# ftdi.net
KiCad netlist of a schematic drawn in Altium Designer
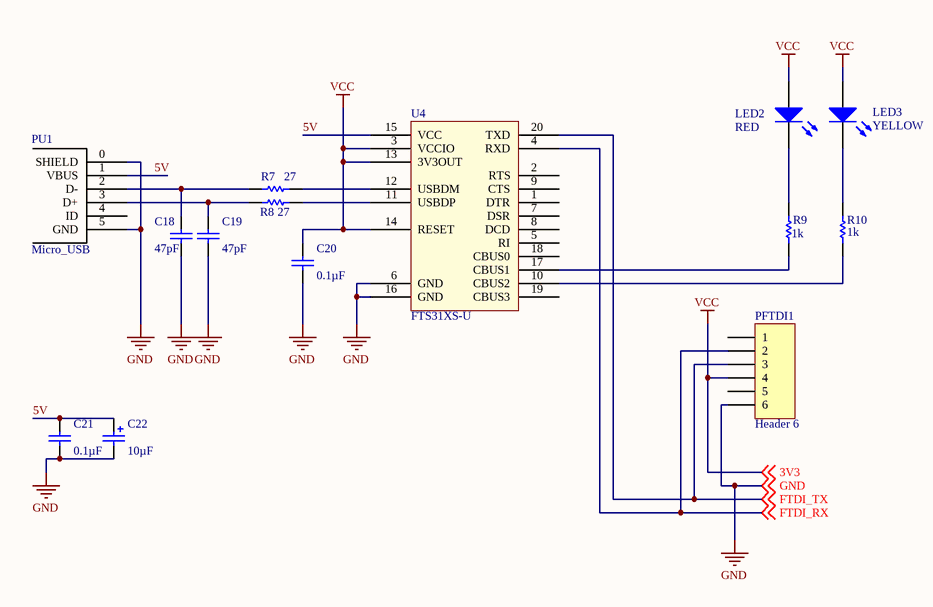
[diagram p0: ftdi.SchDoc]

(export (version "E")
  (design (tool "Eeschema 10.0.6"))
  (components
    (comp (ref "C18")
      (value "47pF")
      (footprint "0805-C")
      (description "Capacitor")
      (fields (field (name "Comment") "Cap") (field (name "PUBLISHER") "Altium Limited"))
      (libsource (lib "Miscellaneous Devices") (part "Cap"))
    )
    (comp (ref "C19")
      (value "47pF")
      (footprint "0805-C")
      (description "Capacitor")
      (fields (field (name "Comment") "Cap") (field (name "PUBLISHER") "Altium Limited"))
      (libsource (lib "Miscellaneous Devices") (part "Cap"))
    )
    (comp (ref "C20")
      (value "0.1µF")
      (footprint "0805-C")
      (description "Capacitor")
      (fields (field (name "Comment") "Cap") (field (name "PUBLISHER") "Altium Limited"))
      (libsource (lib "Miscellaneous Devices") (part "Cap"))
    )
    (comp (ref "C21")
      (value "0.1µF")
      (footprint "0805-C")
      (description "Capacitor")
      (fields (field (name "Comment") "Cap") (field (name "PUBLISHER") "Altium Limited"))
      (libsource (lib "Miscellaneous Devices") (part "Cap"))
    )
    (comp (ref "C22")
      (value "10µF")
      (footprint "0805-TC")
      (description "Polarized Capacitor (Radial)")
      (fields (field (name "Comment") "Cap Pol1") (field (name "PUBLISHER") "Altium Limited"))
      (libsource (lib "Miscellaneous Devices") (part "Cap Pol1"))
    )
    (comp (ref "LED2")
      (value "RED")
      (footprint "0805-LED")
      (description "Typical RED, GREEN, YELLOW, AMBER GaAs LED")
      (fields (field (name "PUBLISHER") "Altium Limited"))
      (libsource (lib "Miscellaneous Devices") (part "LED2"))
    )
    (comp (ref "LED3")
      (value "YELLOW")
      (footprint "0805-LED")
      (description "Typical RED, GREEN, YELLOW, AMBER GaAs LED")
      (fields (field (name "PUBLISHER") "Altium Limited"))
      (libsource (lib "Miscellaneous Devices") (part "LED2"))
    )
    (comp (ref "PFTDI1")
      (value "Header 6")
      (footprint "HDR1X6")
      (description "Header, 6-Pin")
      (fields (field (name "PUBLISHER") "Altium Limited"))
      (libsource (lib "Miscellaneous Connectors") (part "Header 6"))
    )
    (comp (ref "PU1")
      (value "Micro_USB")
      (footprint "Micro_USB")
      (libsource (lib "Micro_USB") (part "Micro_USB"))
    )
    (comp (ref "R7")
      (value "27")
      (footprint "0805-R")
      (description "Resistor")
      (fields (field (name "Comment") "Res1") (field (name "PUBLISHER") "Altium Limited"))
      (libsource (lib "Miscellaneous Devices") (part "Res1"))
    )
    (comp (ref "R8")
      (value "27")
      (footprint "0805-R")
      (description "Resistor")
      (fields (field (name "Comment") "Res1") (field (name "PUBLISHER") "Altium Limited"))
      (libsource (lib "Miscellaneous Devices") (part "Res1"))
    )
    (comp (ref "R9")
      (value "1k")
      (footprint "0805-R")
      (description "Resistor")
      (fields (field (name "Comment") "Res1") (field (name "PUBLISHER") "Altium Limited"))
      (libsource (lib "Miscellaneous Devices") (part "Res1"))
    )
    (comp (ref "R10")
      (value "1k")
      (footprint "0805-R")
      (description "Resistor")
      (fields (field (name "Comment") "Res1") (field (name "PUBLISHER") "Altium Limited"))
      (libsource (lib "Miscellaneous Devices") (part "Res1"))
    )
    (comp (ref "U4")
      (value "FTS31XS-U")
      (footprint "SOP64P570X175-20N")
      (libsource (lib "FTS31XS-U") (part "FTS31XS-U"))
    )
  )
  (nets
    (net (code "1") (name "/5V") (class "Default")
      (node (ref "C21") (pin "2") (pinfunction "2_2") (pintype "passive"))
      (node (ref "C22") (pin "1") (pinfunction "1_1") (pintype "passive"))
      (node (ref "PU1") (pin "1") (pinfunction "VBUS_1") (pintype "passive"))
      (node (ref "U4") (pin "15") (pinfunction "VCC_15") (pintype "passive"))
    )
    (net (code "2") (name "3V3") (class "Default")
      (node (ref "C20") (pin "2") (pinfunction "2_2") (pintype "passive"))
      (node (ref "LED2") (pin "1") (pinfunction "A_1") (pintype "passive"))
      (node (ref "LED3") (pin "1") (pinfunction "A_1") (pintype "passive"))
      (node (ref "PFTDI1") (pin "4") (pinfunction "4_4") (pintype "passive"))
      (node (ref "U4") (pin "13") (pinfunction "3V3OUT_13") (pintype "passive"))
      (node (ref "U4") (pin "14") (pinfunction "RESET_14") (pintype "passive"))
      (node (ref "U4") (pin "3") (pinfunction "VCCIO_3") (pintype "passive"))
    )
    (net (code "3") (name "FTDI_RX") (class "Default")
      (node (ref "PFTDI1") (pin "2") (pinfunction "2_2") (pintype "passive"))
      (node (ref "U4") (pin "4") (pinfunction "RXD_4") (pintype "passive"))
    )
    (net (code "4") (name "FTDI_TX") (class "Default")
      (node (ref "PFTDI1") (pin "3") (pinfunction "3_3") (pintype "passive"))
      (node (ref "U4") (pin "20") (pinfunction "TXD_20") (pintype "passive"))
    )
    (net (code "5") (name "GND") (class "Default")
      (node (ref "C18") (pin "1") (pinfunction "1_1") (pintype "passive"))
      (node (ref "C19") (pin "1") (pinfunction "1_1") (pintype "passive"))
      (node (ref "C20") (pin "1") (pinfunction "1_1") (pintype "passive"))
      (node (ref "C21") (pin "1") (pinfunction "1_1") (pintype "passive"))
      (node (ref "C22") (pin "2") (pinfunction "2_2") (pintype "passive"))
      (node (ref "PFTDI1") (pin "6") (pinfunction "6_6") (pintype "passive"))
      (node (ref "PU1") (pin "0") (pinfunction "SHIELD_0") (pintype "passive"))
      (node (ref "PU1") (pin "5") (pinfunction "GND_5") (pintype "passive"))
      (node (ref "U4") (pin "16") (pinfunction "GND_16") (pintype "passive"))
      (node (ref "U4") (pin "6") (pinfunction "GND_6") (pintype "passive"))
    )
    (net (code "6") (name "Net-(LED2-K)") (class "Default")
      (node (ref "LED2") (pin "2") (pinfunction "K_2") (pintype "passive"))
      (node (ref "R9") (pin "2") (pinfunction "2_2") (pintype "passive"))
    )
    (net (code "7") (name "Net-(LED3-K)") (class "Default")
      (node (ref "LED3") (pin "2") (pinfunction "K_2") (pintype "passive"))
      (node (ref "R10") (pin "2") (pinfunction "2_2") (pintype "passive"))
    )
    (net (code "8") (name "Net-(PU1-D+)") (class "Default")
      (node (ref "C19") (pin "2") (pinfunction "2_2") (pintype "passive"))
      (node (ref "PU1") (pin "3") (pinfunction "D+_3") (pintype "passive"))
      (node (ref "R8") (pin "1") (pinfunction "1_1") (pintype "passive"))
    )
    (net (code "9") (name "Net-(PU1-D-)") (class "Default")
      (node (ref "C18") (pin "2") (pinfunction "2_2") (pintype "passive"))
      (node (ref "PU1") (pin "2") (pinfunction "D-_2") (pintype "passive"))
      (node (ref "R7") (pin "1") (pinfunction "1_1") (pintype "passive"))
    )
    (net (code "10") (name "Net-(U4-CBUS1)") (class "Default")
      (node (ref "R9") (pin "1") (pinfunction "1_1") (pintype "passive"))
      (node (ref "U4") (pin "17") (pinfunction "CBUS1_17") (pintype "passive"))
    )
    (net (code "11") (name "Net-(U4-CBUS2)") (class "Default")
      (node (ref "R10") (pin "1") (pinfunction "1_1") (pintype "passive"))
      (node (ref "U4") (pin "10") (pinfunction "CBUS2_10") (pintype "passive"))
    )
    (net (code "12") (name "Net-(U4-USBDM)") (class "Default")
      (node (ref "R7") (pin "2") (pinfunction "2_2") (pintype "passive"))
      (node (ref "U4") (pin "12") (pinfunction "USBDM_12") (pintype "passive"))
    )
    (net (code "13") (name "Net-(U4-USBDP)") (class "Default")
      (node (ref "R8") (pin "2") (pinfunction "2_2") (pintype "passive"))
      (node (ref "U4") (pin "11") (pinfunction "USBDP_11") (pintype "passive"))
    )
    (net (code "14") (name "unconnected-(PFTDI1-Pad1)") (class "Default")
      (node (ref "PFTDI1") (pin "1") (pinfunction "1_1") (pintype "passive"))
    )
    (net (code "15") (name "unconnected-(PFTDI1-Pad5)") (class "Default")
      (node (ref "PFTDI1") (pin "5") (pinfunction "5_5") (pintype "passive"))
    )
    (net (code "16") (name "unconnected-(PU1-ID-Pad4)") (class "Default")
      (node (ref "PU1") (pin "4") (pinfunction "ID_4") (pintype "passive"))
    )
    (net (code "17") (name "unconnected-(U4-CBUS0-Pad18)") (class "Default")
      (node (ref "U4") (pin "18") (pinfunction "CBUS0_18") (pintype "passive"))
    )
    (net (code "18") (name "unconnected-(U4-CBUS3-Pad19)") (class "Default")
      (node (ref "U4") (pin "19") (pinfunction "CBUS3_19") (pintype "passive"))
    )
    (net (code "19") (name "unconnected-(U4-CTS-Pad9)") (class "Default")
      (node (ref "U4") (pin "9") (pinfunction "CTS_9") (pintype "passive"))
    )
    (net (code "20") (name "unconnected-(U4-DCD-Pad8)") (class "Default")
      (node (ref "U4") (pin "8") (pinfunction "DCD_8") (pintype "passive"))
    )
    (net (code "21") (name "unconnected-(U4-DSR-Pad7)") (class "Default")
      (node (ref "U4") (pin "7") (pinfunction "DSR_7") (pintype "passive"))
    )
    (net (code "22") (name "unconnected-(U4-DTR-Pad1)") (class "Default")
      (node (ref "U4") (pin "1") (pinfunction "DTR_1") (pintype "passive"))
    )
    (net (code "23") (name "unconnected-(U4-RI-Pad5)") (class "Default")
      (node (ref "U4") (pin "5") (pinfunction "RI_5") (pintype "passive"))
    )
    (net (code "24") (name "unconnected-(U4-RTS-Pad2)") (class "Default")
      (node (ref "U4") (pin "2") (pinfunction "RTS_2") (pintype "passive"))
    )
  )
)
